# sodimm_perf.net
KiCad netlist of a schematic drawn in EAGLE
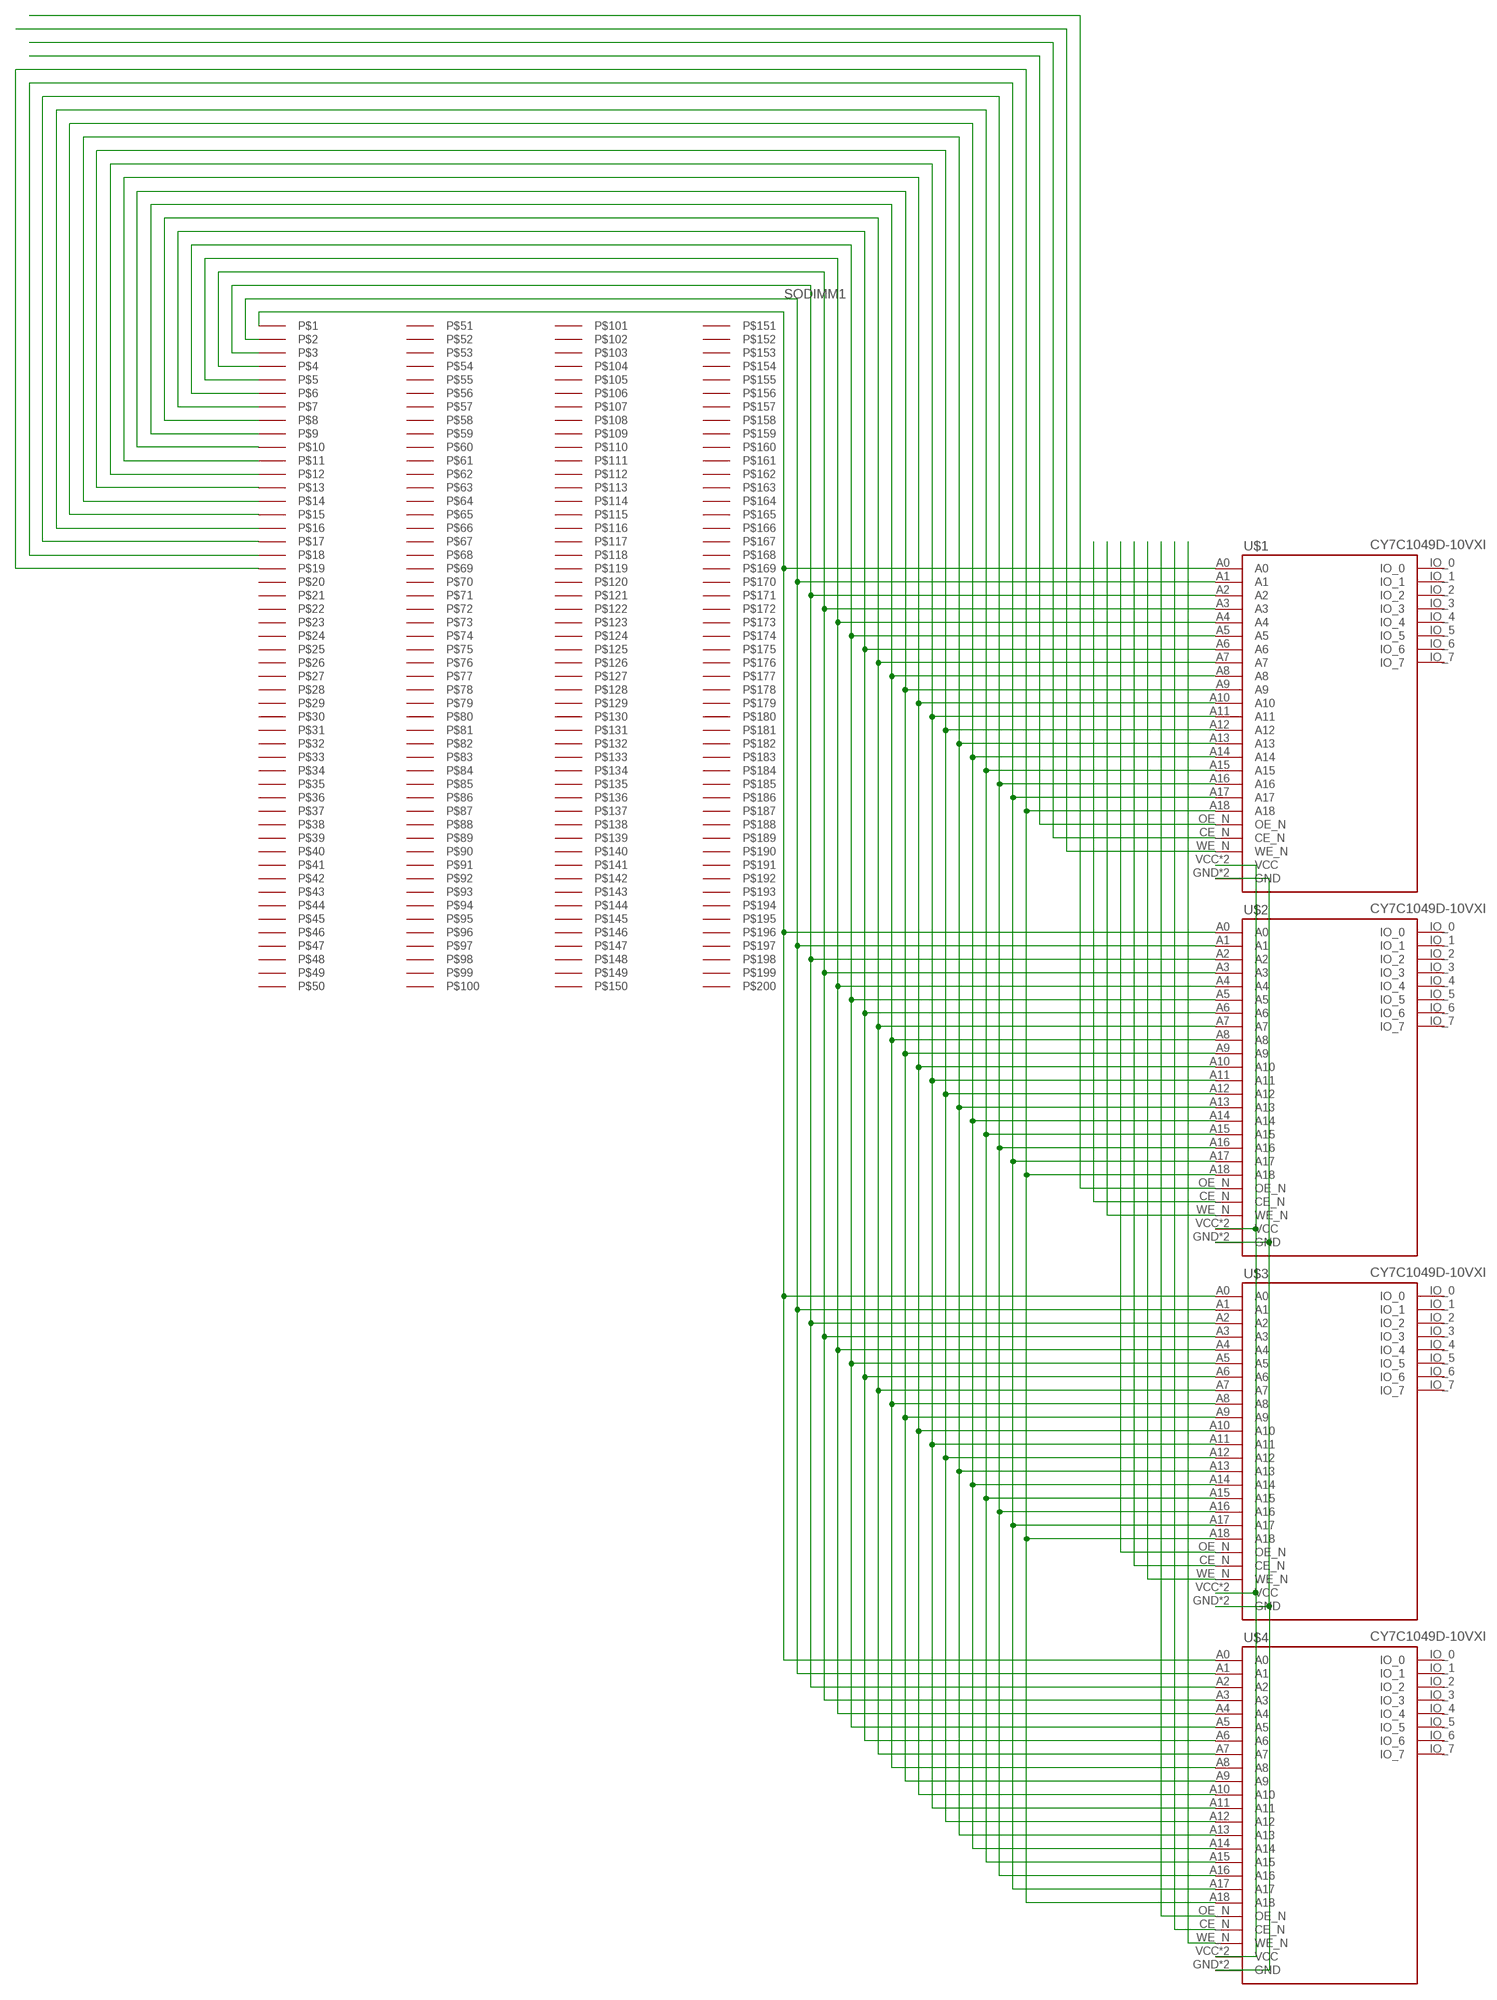
[diagram p0: schematic, sheet 1]

(export (version "E")
  (design (tool "Eeschema 10.0.6"))
  (components
    (comp (ref "SODIMM1")
      (value "SODIMM_BOARD")
      (footprint "eagle-import:SODIMM_BOARD-67.6X42.5")
      (libsource (lib "eagle-import") (part "SODIMM_BOARD"))
    )
    (comp (ref "U$1")
      (value "CY7C1049D-10VXI")
      (footprint "eagle-import:SOJ36")
      (libsource (lib "eagle-import") (part "CY7C1049D-10VXI"))
    )
    (comp (ref "U$2")
      (value "CY7C1049D-10VXI")
      (footprint "eagle-import:SOJ36")
      (libsource (lib "eagle-import") (part "CY7C1049D-10VXI"))
    )
    (comp (ref "U$3")
      (value "CY7C1049D-10VXI")
      (footprint "eagle-import:SOJ36")
      (libsource (lib "eagle-import") (part "CY7C1049D-10VXI"))
    )
    (comp (ref "U$4")
      (value "CY7C1049D-10VXI")
      (footprint "eagle-import:SOJ36")
      (libsource (lib "eagle-import") (part "CY7C1049D-10VXI"))
    )
  )
  (nets
    (net (code "1") (name "Net-(SODIMM1-P$1)") (class "Default")
      (node (ref "SODIMM1") (pin "1") (pinfunction "P$1_1") (pintype "bidirectional"))
      (node (ref "U$1") (pin "A0") (pinfunction "A0_A0") (pintype "input"))
      (node (ref "U$2") (pin "A0") (pinfunction "A0_A0") (pintype "input"))
      (node (ref "U$3") (pin "A0") (pinfunction "A0_A0") (pintype "input"))
      (node (ref "U$4") (pin "A0") (pinfunction "A0_A0") (pintype "input"))
    )
    (net (code "2") (name "Net-(SODIMM1-P$2)") (class "Default")
      (node (ref "SODIMM1") (pin "2") (pinfunction "P$2_2") (pintype "bidirectional"))
      (node (ref "U$1") (pin "A1") (pinfunction "A1_A1") (pintype "input"))
      (node (ref "U$2") (pin "A1") (pinfunction "A1_A1") (pintype "input"))
      (node (ref "U$3") (pin "A1") (pinfunction "A1_A1") (pintype "input"))
      (node (ref "U$4") (pin "A1") (pinfunction "A1_A1") (pintype "input"))
    )
    (net (code "3") (name "Net-(SODIMM1-P$3)") (class "Default")
      (node (ref "SODIMM1") (pin "3") (pinfunction "P$3_3") (pintype "bidirectional"))
      (node (ref "U$1") (pin "A2") (pinfunction "A2_A2") (pintype "input"))
      (node (ref "U$2") (pin "A2") (pinfunction "A2_A2") (pintype "input"))
      (node (ref "U$3") (pin "A2") (pinfunction "A2_A2") (pintype "input"))
      (node (ref "U$4") (pin "A2") (pinfunction "A2_A2") (pintype "input"))
    )
    (net (code "4") (name "Net-(SODIMM1-P$4)") (class "Default")
      (node (ref "SODIMM1") (pin "4") (pinfunction "P$4_4") (pintype "bidirectional"))
      (node (ref "U$1") (pin "A3") (pinfunction "A3_A3") (pintype "input"))
      (node (ref "U$2") (pin "A3") (pinfunction "A3_A3") (pintype "input"))
      (node (ref "U$3") (pin "A3") (pinfunction "A3_A3") (pintype "input"))
      (node (ref "U$4") (pin "A3") (pinfunction "A3_A3") (pintype "input"))
    )
    (net (code "5") (name "Net-(SODIMM1-P$5)") (class "Default")
      (node (ref "SODIMM1") (pin "5") (pinfunction "P$5_5") (pintype "bidirectional"))
      (node (ref "U$1") (pin "A4") (pinfunction "A4_A4") (pintype "input"))
      (node (ref "U$2") (pin "A4") (pinfunction "A4_A4") (pintype "input"))
      (node (ref "U$3") (pin "A4") (pinfunction "A4_A4") (pintype "input"))
      (node (ref "U$4") (pin "A4") (pinfunction "A4_A4") (pintype "input"))
    )
    (net (code "6") (name "Net-(SODIMM1-P$6)") (class "Default")
      (node (ref "SODIMM1") (pin "6") (pinfunction "P$6_6") (pintype "bidirectional"))
      (node (ref "U$1") (pin "A5") (pinfunction "A5_A5") (pintype "input"))
      (node (ref "U$2") (pin "A5") (pinfunction "A5_A5") (pintype "input"))
      (node (ref "U$3") (pin "A5") (pinfunction "A5_A5") (pintype "input"))
      (node (ref "U$4") (pin "A5") (pinfunction "A5_A5") (pintype "input"))
    )
    (net (code "7") (name "Net-(SODIMM1-P$7)") (class "Default")
      (node (ref "SODIMM1") (pin "7") (pinfunction "P$7_7") (pintype "bidirectional"))
      (node (ref "U$1") (pin "A6") (pinfunction "A6_A6") (pintype "input"))
      (node (ref "U$2") (pin "A6") (pinfunction "A6_A6") (pintype "input"))
      (node (ref "U$3") (pin "A6") (pinfunction "A6_A6") (pintype "input"))
      (node (ref "U$4") (pin "A6") (pinfunction "A6_A6") (pintype "input"))
    )
    (net (code "8") (name "Net-(SODIMM1-P$8)") (class "Default")
      (node (ref "SODIMM1") (pin "8") (pinfunction "P$8_8") (pintype "bidirectional"))
      (node (ref "U$1") (pin "A7") (pinfunction "A7_A7") (pintype "input"))
      (node (ref "U$2") (pin "A7") (pinfunction "A7_A7") (pintype "input"))
      (node (ref "U$3") (pin "A7") (pinfunction "A7_A7") (pintype "input"))
      (node (ref "U$4") (pin "A7") (pinfunction "A7_A7") (pintype "input"))
    )
    (net (code "9") (name "Net-(SODIMM1-P$9)") (class "Default")
      (node (ref "SODIMM1") (pin "9") (pinfunction "P$9_9") (pintype "bidirectional"))
      (node (ref "U$1") (pin "A8") (pinfunction "A8_A8") (pintype "input"))
      (node (ref "U$2") (pin "A8") (pinfunction "A8_A8") (pintype "input"))
      (node (ref "U$3") (pin "A8") (pinfunction "A8_A8") (pintype "input"))
      (node (ref "U$4") (pin "A8") (pinfunction "A8_A8") (pintype "input"))
    )
    (net (code "10") (name "Net-(SODIMM1-P$10)") (class "Default")
      (node (ref "SODIMM1") (pin "10") (pinfunction "P$10_10") (pintype "bidirectional"))
      (node (ref "U$1") (pin "A9") (pinfunction "A9_A9") (pintype "input"))
      (node (ref "U$2") (pin "A9") (pinfunction "A9_A9") (pintype "input"))
      (node (ref "U$3") (pin "A9") (pinfunction "A9_A9") (pintype "input"))
      (node (ref "U$4") (pin "A9") (pinfunction "A9_A9") (pintype "input"))
    )
    (net (code "11") (name "Net-(SODIMM1-P$11)") (class "Default")
      (node (ref "SODIMM1") (pin "11") (pinfunction "P$11_11") (pintype "bidirectional"))
      (node (ref "U$1") (pin "A10") (pinfunction "A10_A10") (pintype "input"))
      (node (ref "U$2") (pin "A10") (pinfunction "A10_A10") (pintype "input"))
      (node (ref "U$3") (pin "A10") (pinfunction "A10_A10") (pintype "input"))
      (node (ref "U$4") (pin "A10") (pinfunction "A10_A10") (pintype "input"))
    )
    (net (code "12") (name "Net-(SODIMM1-P$12)") (class "Default")
      (node (ref "SODIMM1") (pin "12") (pinfunction "P$12_12") (pintype "bidirectional"))
      (node (ref "U$1") (pin "A11") (pinfunction "A11_A11") (pintype "input"))
      (node (ref "U$2") (pin "A11") (pinfunction "A11_A11") (pintype "input"))
      (node (ref "U$3") (pin "A11") (pinfunction "A11_A11") (pintype "input"))
      (node (ref "U$4") (pin "A11") (pinfunction "A11_A11") (pintype "input"))
    )
    (net (code "13") (name "Net-(SODIMM1-P$13)") (class "Default")
      (node (ref "SODIMM1") (pin "13") (pinfunction "P$13_13") (pintype "bidirectional"))
      (node (ref "U$1") (pin "A12") (pinfunction "A12_A12") (pintype "input"))
      (node (ref "U$2") (pin "A12") (pinfunction "A12_A12") (pintype "input"))
      (node (ref "U$3") (pin "A12") (pinfunction "A12_A12") (pintype "input"))
      (node (ref "U$4") (pin "A12") (pinfunction "A12_A12") (pintype "input"))
    )
    (net (code "14") (name "Net-(SODIMM1-P$14)") (class "Default")
      (node (ref "SODIMM1") (pin "14") (pinfunction "P$14_14") (pintype "bidirectional"))
      (node (ref "U$1") (pin "A13") (pinfunction "A13_A13") (pintype "input"))
      (node (ref "U$2") (pin "A13") (pinfunction "A13_A13") (pintype "input"))
      (node (ref "U$3") (pin "A13") (pinfunction "A13_A13") (pintype "input"))
      (node (ref "U$4") (pin "A13") (pinfunction "A13_A13") (pintype "input"))
    )
    (net (code "15") (name "Net-(SODIMM1-P$15)") (class "Default")
      (node (ref "SODIMM1") (pin "15") (pinfunction "P$15_15") (pintype "bidirectional"))
      (node (ref "U$1") (pin "A14") (pinfunction "A14_A14") (pintype "input"))
      (node (ref "U$2") (pin "A14") (pinfunction "A14_A14") (pintype "input"))
      (node (ref "U$3") (pin "A14") (pinfunction "A14_A14") (pintype "input"))
      (node (ref "U$4") (pin "A14") (pinfunction "A14_A14") (pintype "input"))
    )
    (net (code "16") (name "Net-(SODIMM1-P$16)") (class "Default")
      (node (ref "SODIMM1") (pin "16") (pinfunction "P$16_16") (pintype "bidirectional"))
      (node (ref "U$1") (pin "A15") (pinfunction "A15_A15") (pintype "input"))
      (node (ref "U$2") (pin "A15") (pinfunction "A15_A15") (pintype "input"))
      (node (ref "U$3") (pin "A15") (pinfunction "A15_A15") (pintype "input"))
      (node (ref "U$4") (pin "A15") (pinfunction "A15_A15") (pintype "input"))
    )
    (net (code "17") (name "Net-(SODIMM1-P$17)") (class "Default")
      (node (ref "SODIMM1") (pin "17") (pinfunction "P$17_17") (pintype "bidirectional"))
      (node (ref "U$1") (pin "A16") (pinfunction "A16_A16") (pintype "input"))
      (node (ref "U$2") (pin "A16") (pinfunction "A16_A16") (pintype "input"))
      (node (ref "U$3") (pin "A16") (pinfunction "A16_A16") (pintype "input"))
      (node (ref "U$4") (pin "A16") (pinfunction "A16_A16") (pintype "input"))
    )
    (net (code "18") (name "Net-(SODIMM1-P$18)") (class "Default")
      (node (ref "SODIMM1") (pin "18") (pinfunction "P$18_18") (pintype "bidirectional"))
      (node (ref "U$1") (pin "A17") (pinfunction "A17_A17") (pintype "input"))
      (node (ref "U$2") (pin "A17") (pinfunction "A17_A17") (pintype "input"))
      (node (ref "U$3") (pin "A17") (pinfunction "A17_A17") (pintype "input"))
      (node (ref "U$4") (pin "A17") (pinfunction "A17_A17") (pintype "input"))
    )
    (net (code "19") (name "Net-(SODIMM1-P$19)") (class "Default")
      (node (ref "SODIMM1") (pin "19") (pinfunction "P$19_19") (pintype "bidirectional"))
      (node (ref "U$1") (pin "A18") (pinfunction "A18_A18") (pintype "input"))
      (node (ref "U$2") (pin "A18") (pinfunction "A18_A18") (pintype "input"))
      (node (ref "U$3") (pin "A18") (pinfunction "A18_A18") (pintype "input"))
      (node (ref "U$4") (pin "A18") (pinfunction "A18_A18") (pintype "input"))
    )
    (net (code "20") (name "Net-(U$1-GND-PadGND_)") (class "Default")
      (node (ref "U$1") (pin "GND") (pinfunction "GND_GND") (pintype "power_in"))
      (node (ref "U$1") (pin "GND_") (pinfunction "GND_GND_") (pintype "power_in"))
      (node (ref "U$2") (pin "GND") (pinfunction "GND_GND") (pintype "power_in"))
      (node (ref "U$2") (pin "GND_") (pinfunction "GND_GND_") (pintype "power_in"))
      (node (ref "U$3") (pin "GND") (pinfunction "GND_GND") (pintype "power_in"))
      (node (ref "U$3") (pin "GND_") (pinfunction "GND_GND_") (pintype "power_in"))
      (node (ref "U$4") (pin "GND") (pinfunction "GND_GND") (pintype "power_in"))
      (node (ref "U$4") (pin "GND_") (pinfunction "GND_GND_") (pintype "power_in"))
    )
    (net (code "21") (name "Net-(U$1-PadVCC)") (class "Default")
      (node (ref "U$1") (pin "VCC") (pinfunction "VCC_VCC") (pintype "power_in"))
      (node (ref "U$1") (pin "VCC_") (pinfunction "VCC_VCC_") (pintype "power_in"))
      (node (ref "U$2") (pin "VCC") (pinfunction "VCC_VCC") (pintype "power_in"))
      (node (ref "U$2") (pin "VCC_") (pinfunction "VCC_VCC_") (pintype "power_in"))
      (node (ref "U$3") (pin "VCC") (pinfunction "VCC_VCC") (pintype "power_in"))
      (node (ref "U$3") (pin "VCC_") (pinfunction "VCC_VCC_") (pintype "power_in"))
      (node (ref "U$4") (pin "VCC") (pinfunction "VCC_VCC") (pintype "power_in"))
      (node (ref "U$4") (pin "VCC_") (pinfunction "VCC_VCC_") (pintype "power_in"))
    )
    (net (code "22") (name "unconnected-(SODIMM1-P$20-Pad20)") (class "Default")
      (node (ref "SODIMM1") (pin "20") (pinfunction "P$20_20") (pintype "bidirectional"))
    )
    (net (code "23") (name "unconnected-(SODIMM1-P$21-Pad21)") (class "Default")
      (node (ref "SODIMM1") (pin "21") (pinfunction "P$21_21") (pintype "bidirectional"))
    )
    (net (code "24") (name "unconnected-(SODIMM1-P$22-Pad22)") (class "Default")
      (node (ref "SODIMM1") (pin "22") (pinfunction "P$22_22") (pintype "bidirectional"))
    )
    (net (code "25") (name "unconnected-(SODIMM1-P$23-Pad23)") (class "Default")
      (node (ref "SODIMM1") (pin "23") (pinfunction "P$23_23") (pintype "bidirectional"))
    )
    (net (code "26") (name "unconnected-(SODIMM1-P$24-Pad24)") (class "Default")
      (node (ref "SODIMM1") (pin "24") (pinfunction "P$24_24") (pintype "bidirectional"))
    )
    (net (code "27") (name "unconnected-(SODIMM1-P$25-Pad25)") (class "Default")
      (node (ref "SODIMM1") (pin "25") (pinfunction "P$25_25") (pintype "bidirectional"))
    )
    (net (code "28") (name "unconnected-(SODIMM1-P$26-Pad26)") (class "Default")
      (node (ref "SODIMM1") (pin "26") (pinfunction "P$26_26") (pintype "bidirectional"))
    )
    (net (code "29") (name "unconnected-(SODIMM1-P$27-Pad27)") (class "Default")
      (node (ref "SODIMM1") (pin "27") (pinfunction "P$27_27") (pintype "bidirectional"))
    )
    (net (code "30") (name "unconnected-(SODIMM1-P$28-Pad28)") (class "Default")
      (node (ref "SODIMM1") (pin "28") (pinfunction "P$28_28") (pintype "bidirectional"))
    )
    (net (code "31") (name "unconnected-(SODIMM1-P$29-Pad29)") (class "Default")
      (node (ref "SODIMM1") (pin "29") (pinfunction "P$29_29") (pintype "bidirectional"))
    )
    (net (code "32") (name "unconnected-(SODIMM1-P$30-Pad30)") (class "Default")
      (node (ref "SODIMM1") (pin "30") (pinfunction "P$30_30") (pintype "bidirectional"))
    )
    (net (code "33") (name "unconnected-(SODIMM1-P$31-Pad31)") (class "Default")
      (node (ref "SODIMM1") (pin "31") (pinfunction "P$31_31") (pintype "bidirectional"))
    )
    (net (code "34") (name "unconnected-(SODIMM1-P$32-Pad32)") (class "Default")
      (node (ref "SODIMM1") (pin "32") (pinfunction "P$32_32") (pintype "bidirectional"))
    )
    (net (code "35") (name "unconnected-(SODIMM1-P$33-Pad33)") (class "Default")
      (node (ref "SODIMM1") (pin "33") (pinfunction "P$33_33") (pintype "bidirectional"))
    )
    (net (code "36") (name "unconnected-(SODIMM1-P$34-Pad34)") (class "Default")
      (node (ref "SODIMM1") (pin "34") (pinfunction "P$34_34") (pintype "bidirectional"))
    )
    (net (code "37") (name "unconnected-(SODIMM1-P$35-Pad35)") (class "Default")
      (node (ref "SODIMM1") (pin "35") (pinfunction "P$35_35") (pintype "bidirectional"))
    )
    (net (code "38") (name "unconnected-(SODIMM1-P$36-Pad36)") (class "Default")
      (node (ref "SODIMM1") (pin "36") (pinfunction "P$36_36") (pintype "bidirectional"))
    )
    (net (code "39") (name "unconnected-(SODIMM1-P$37-Pad37)") (class "Default")
      (node (ref "SODIMM1") (pin "37") (pinfunction "P$37_37") (pintype "bidirectional"))
    )
    (net (code "40") (name "unconnected-(SODIMM1-P$38-Pad38)") (class "Default")
      (node (ref "SODIMM1") (pin "38") (pinfunction "P$38_38") (pintype "bidirectional"))
    )
    (net (code "41") (name "unconnected-(SODIMM1-P$39-Pad39)") (class "Default")
      (node (ref "SODIMM1") (pin "39") (pinfunction "P$39_39") (pintype "bidirectional"))
    )
    (net (code "42") (name "unconnected-(SODIMM1-P$40-Pad40)") (class "Default")
      (node (ref "SODIMM1") (pin "40") (pinfunction "P$40_40") (pintype "bidirectional"))
    )
    (net (code "43") (name "unconnected-(SODIMM1-P$41-Pad41)") (class "Default")
      (node (ref "SODIMM1") (pin "41") (pinfunction "P$41_41") (pintype "bidirectional"))
    )
    (net (code "44") (name "unconnected-(SODIMM1-P$42-Pad42)") (class "Default")
      (node (ref "SODIMM1") (pin "42") (pinfunction "P$42_42") (pintype "bidirectional"))
    )
    (net (code "45") (name "unconnected-(SODIMM1-P$43-Pad43)") (class "Default")
      (node (ref "SODIMM1") (pin "43") (pinfunction "P$43_43") (pintype "bidirectional"))
    )
    (net (code "46") (name "unconnected-(SODIMM1-P$44-Pad44)") (class "Default")
      (node (ref "SODIMM1") (pin "44") (pinfunction "P$44_44") (pintype "bidirectional"))
    )
    (net (code "47") (name "unconnected-(SODIMM1-P$45-Pad45)") (class "Default")
      (node (ref "SODIMM1") (pin "45") (pinfunction "P$45_45") (pintype "bidirectional"))
    )
    (net (code "48") (name "unconnected-(SODIMM1-P$46-Pad46)") (class "Default")
      (node (ref "SODIMM1") (pin "46") (pinfunction "P$46_46") (pintype "bidirectional"))
    )
    (net (code "49") (name "unconnected-(SODIMM1-P$47-Pad47)") (class "Default")
      (node (ref "SODIMM1") (pin "47") (pinfunction "P$47_47") (pintype "bidirectional"))
    )
    (net (code "50") (name "unconnected-(SODIMM1-P$48-Pad48)") (class "Default")
      (node (ref "SODIMM1") (pin "48") (pinfunction "P$48_48") (pintype "bidirectional"))
    )
    (net (code "51") (name "unconnected-(SODIMM1-P$49-Pad49)") (class "Default")
      (node (ref "SODIMM1") (pin "49") (pinfunction "P$49_49") (pintype "bidirectional"))
    )
    (net (code "52") (name "unconnected-(SODIMM1-P$50-Pad50)") (class "Default")
      (node (ref "SODIMM1") (pin "50") (pinfunction "P$50_50") (pintype "bidirectional"))
    )
    (net (code "53") (name "unconnected-(SODIMM1-P$51-Pad51)") (class "Default")
      (node (ref "SODIMM1") (pin "51") (pinfunction "P$51_51") (pintype "bidirectional"))
    )
    (net (code "54") (name "unconnected-(SODIMM1-P$52-Pad52)") (class "Default")
      (node (ref "SODIMM1") (pin "52") (pinfunction "P$52_52") (pintype "bidirectional"))
    )
    (net (code "55") (name "unconnected-(SODIMM1-P$53-Pad53)") (class "Default")
      (node (ref "SODIMM1") (pin "53") (pinfunction "P$53_53") (pintype "bidirectional"))
    )
    (net (code "56") (name "unconnected-(SODIMM1-P$54-Pad54)") (class "Default")
      (node (ref "SODIMM1") (pin "54") (pinfunction "P$54_54") (pintype "bidirectional"))
    )
    (net (code "57") (name "unconnected-(SODIMM1-P$55-Pad55)") (class "Default")
      (node (ref "SODIMM1") (pin "55") (pinfunction "P$55_55") (pintype "bidirectional"))
    )
    (net (code "58") (name "unconnected-(SODIMM1-P$56-Pad56)") (class "Default")
      (node (ref "SODIMM1") (pin "56") (pinfunction "P$56_56") (pintype "bidirectional"))
    )
    (net (code "59") (name "unconnected-(SODIMM1-P$57-Pad57)") (class "Default")
      (node (ref "SODIMM1") (pin "57") (pinfunction "P$57_57") (pintype "bidirectional"))
    )
    (net (code "60") (name "unconnected-(SODIMM1-P$58-Pad58)") (class "Default")
      (node (ref "SODIMM1") (pin "58") (pinfunction "P$58_58") (pintype "bidirectional"))
    )
    (net (code "61") (name "unconnected-(SODIMM1-P$59-Pad59)") (class "Default")
      (node (ref "SODIMM1") (pin "59") (pinfunction "P$59_59") (pintype "bidirectional"))
    )
    (net (code "62") (name "unconnected-(SODIMM1-P$60-Pad60)") (class "Default")
      (node (ref "SODIMM1") (pin "60") (pinfunction "P$60_60") (pintype "bidirectional"))
    )
    (net (code "63") (name "unconnected-(SODIMM1-P$61-Pad61)") (class "Default")
      (node (ref "SODIMM1") (pin "61") (pinfunction "P$61_61") (pintype "bidirectional"))
    )
    (net (code "64") (name "unconnected-(SODIMM1-P$62-Pad62)") (class "Default")
      (node (ref "SODIMM1") (pin "62") (pinfunction "P$62_62") (pintype "bidirectional"))
    )
    (net (code "65") (name "unconnected-(SODIMM1-P$63-Pad63)") (class "Default")
      (node (ref "SODIMM1") (pin "63") (pinfunction "P$63_63") (pintype "bidirectional"))
    )
    (net (code "66") (name "unconnected-(SODIMM1-P$64-Pad64)") (class "Default")
      (node (ref "SODIMM1") (pin "64") (pinfunction "P$64_64") (pintype "bidirectional"))
    )
    (net (code "67") (name "unconnected-(SODIMM1-P$65-Pad65)") (class "Default")
      (node (ref "SODIMM1") (pin "65") (pinfunction "P$65_65") (pintype "bidirectional"))
    )
    (net (code "68") (name "unconnected-(SODIMM1-P$66-Pad66)") (class "Default")
      (node (ref "SODIMM1") (pin "66") (pinfunction "P$66_66") (pintype "bidirectional"))
    )
    (net (code "69") (name "unconnected-(SODIMM1-P$67-Pad67)") (class "Default")
      (node (ref "SODIMM1") (pin "67") (pinfunction "P$67_67") (pintype "bidirectional"))
    )
    (net (code "70") (name "unconnected-(SODIMM1-P$68-Pad68)") (class "Default")
      (node (ref "SODIMM1") (pin "68") (pinfunction "P$68_68") (pintype "bidirectional"))
    )
    (net (code "71") (name "unconnected-(SODIMM1-P$69-Pad69)") (class "Default")
      (node (ref "SODIMM1") (pin "69") (pinfunction "P$69_69") (pintype "bidirectional"))
    )
    (net (code "72") (name "unconnected-(SODIMM1-P$70-Pad70)") (class "Default")
      (node (ref "SODIMM1") (pin "70") (pinfunction "P$70_70") (pintype "bidirectional"))
    )
    (net (code "73") (name "unconnected-(SODIMM1-P$71-Pad71)") (class "Default")
      (node (ref "SODIMM1") (pin "71") (pinfunction "P$71_71") (pintype "bidirectional"))
    )
    (net (code "74") (name "unconnected-(SODIMM1-P$72-Pad72)") (class "Default")
      (node (ref "SODIMM1") (pin "72") (pinfunction "P$72_72") (pintype "bidirectional"))
    )
    (net (code "75") (name "unconnected-(SODIMM1-P$73-Pad73)") (class "Default")
      (node (ref "SODIMM1") (pin "73") (pinfunction "P$73_73") (pintype "bidirectional"))
    )
    (net (code "76") (name "unconnected-(SODIMM1-P$74-Pad74)") (class "Default")
      (node (ref "SODIMM1") (pin "74") (pinfunction "P$74_74") (pintype "bidirectional"))
    )
    (net (code "77") (name "unconnected-(SODIMM1-P$75-Pad75)") (class "Default")
      (node (ref "SODIMM1") (pin "75") (pinfunction "P$75_75") (pintype "bidirectional"))
    )
    (net (code "78") (name "unconnected-(SODIMM1-P$76-Pad76)") (class "Default")
      (node (ref "SODIMM1") (pin "76") (pinfunction "P$76_76") (pintype "bidirectional"))
    )
    (net (code "79") (name "unconnected-(SODIMM1-P$77-Pad77)") (class "Default")
      (node (ref "SODIMM1") (pin "77") (pinfunction "P$77_77") (pintype "bidirectional"))
    )
    (net (code "80") (name "unconnected-(SODIMM1-P$78-Pad78)") (class "Default")
      (node (ref "SODIMM1") (pin "78") (pinfunction "P$78_78") (pintype "bidirectional"))
    )
    (net (code "81") (name "unconnected-(SODIMM1-P$79-Pad79)") (class "Default")
      (node (ref "SODIMM1") (pin "79") (pinfunction "P$79_79") (pintype "bidirectional"))
    )
    (net (code "82") (name "unconnected-(SODIMM1-P$80-Pad80)") (class "Default")
      (node (ref "SODIMM1") (pin "80") (pinfunction "P$80_80") (pintype "bidirectional"))
    )
    (net (code "83") (name "unconnected-(SODIMM1-P$81-Pad81)") (class "Default")
      (node (ref "SODIMM1") (pin "81") (pinfunction "P$81_81") (pintype "bidirectional"))
    )
    (net (code "84") (name "unconnected-(SODIMM1-P$82-Pad82)") (class "Default")
      (node (ref "SODIMM1") (pin "82") (pinfunction "P$82_82") (pintype "bidirectional"))
    )
    (net (code "85") (name "unconnected-(SODIMM1-P$83-Pad83)") (class "Default")
      (node (ref "SODIMM1") (pin "83") (pinfunction "P$83_83") (pintype "bidirectional"))
    )
    (net (code "86") (name "unconnected-(SODIMM1-P$84-Pad84)") (class "Default")
      (node (ref "SODIMM1") (pin "84") (pinfunction "P$84_84") (pintype "bidirectional"))
    )
    (net (code "87") (name "unconnected-(SODIMM1-P$85-Pad85)") (class "Default")
      (node (ref "SODIMM1") (pin "85") (pinfunction "P$85_85") (pintype "bidirectional"))
    )
    (net (code "88") (name "unconnected-(SODIMM1-P$86-Pad86)") (class "Default")
      (node (ref "SODIMM1") (pin "86") (pinfunction "P$86_86") (pintype "bidirectional"))
    )
    (net (code "89") (name "unconnected-(SODIMM1-P$87-Pad87)") (class "Default")
      (node (ref "SODIMM1") (pin "87") (pinfunction "P$87_87") (pintype "bidirectional"))
    )
    (net (code "90") (name "unconnected-(SODIMM1-P$88-Pad88)") (class "Default")
      (node (ref "SODIMM1") (pin "88") (pinfunction "P$88_88") (pintype "bidirectional"))
    )
    (net (code "91") (name "unconnected-(SODIMM1-P$89-Pad89)") (class "Default")
      (node (ref "SODIMM1") (pin "89") (pinfunction "P$89_89") (pintype "bidirectional"))
    )
    (net (code "92") (name "unconnected-(SODIMM1-P$90-Pad90)") (class "Default")
      (node (ref "SODIMM1") (pin "90") (pinfunction "P$90_90") (pintype "bidirectional"))
    )
    (net (code "93") (name "unconnected-(SODIMM1-P$91-Pad91)") (class "Default")
      (node (ref "SODIMM1") (pin "91") (pinfunction "P$91_91") (pintype "bidirectional"))
    )
    (net (code "94") (name "unconnected-(SODIMM1-P$92-Pad92)") (class "Default")
      (node (ref "SODIMM1") (pin "92") (pinfunction "P$92_92") (pintype "bidirectional"))
    )
    (net (code "95") (name "unconnected-(SODIMM1-P$93-Pad93)") (class "Default")
      (node (ref "SODIMM1") (pin "93") (pinfunction "P$93_93") (pintype "bidirectional"))
    )
    (net (code "96") (name "unconnected-(SODIMM1-P$94-Pad94)") (class "Default")
      (node (ref "SODIMM1") (pin "94") (pinfunction "P$94_94") (pintype "bidirectional"))
    )
    (net (code "97") (name "unconnected-(SODIMM1-P$95-Pad95)") (class "Default")
      (node (ref "SODIMM1") (pin "95") (pinfunction "P$95_95") (pintype "bidirectional"))
    )
    (net (code "98") (name "unconnected-(SODIMM1-P$96-Pad96)") (class "Default")
      (node (ref "SODIMM1") (pin "96") (pinfunction "P$96_96") (pintype "bidirectional"))
    )
    (net (code "99") (name "unconnected-(SODIMM1-P$97-Pad97)") (class "Default")
      (node (ref "SODIMM1") (pin "97") (pinfunction "P$97_97") (pintype "bidirectional"))
    )
    (net (code "100") (name "unconnected-(SODIMM1-P$98-Pad98)") (class "Default")
      (node (ref "SODIMM1") (pin "98") (pinfunction "P$98_98") (pintype "bidirectional"))
    )
    (net (code "101") (name "unconnected-(SODIMM1-P$99-Pad99)") (class "Default")
      (node (ref "SODIMM1") (pin "99") (pinfunction "P$99_99") (pintype "bidirectional"))
    )
    (net (code "102") (name "unconnected-(SODIMM1-P$100-Pad100)") (class "Default")
      (node (ref "SODIMM1") (pin "100") (pinfunction "P$100_100") (pintype "bidirectional"))
    )
    (net (code "103") (name "unconnected-(SODIMM1-P$101-Pad101)") (class "Default")
      (node (ref "SODIMM1") (pin "101") (pinfunction "P$101_101") (pintype "bidirectional"))
    )
    (net (code "104") (name "unconnected-(SODIMM1-P$102-Pad102)") (class "Default")
      (node (ref "SODIMM1") (pin "102") (pinfunction "P$102_102") (pintype "bidirectional"))
    )
    (net (code "105") (name "unconnected-(SODIMM1-P$103-Pad103)") (class "Default")
      (node (ref "SODIMM1") (pin "103") (pinfunction "P$103_103") (pintype "bidirectional"))
    )
    (net (code "106") (name "unconnected-(SODIMM1-P$104-Pad104)") (class "Default")
      (node (ref "SODIMM1") (pin "104") (pinfunction "P$104_104") (pintype "bidirectional"))
    )
    (net (code "107") (name "unconnected-(SODIMM1-P$105-Pad105)") (class "Default")
      (node (ref "SODIMM1") (pin "105") (pinfunction "P$105_105") (pintype "bidirectional"))
    )
    (net (code "108") (name "unconnected-(SODIMM1-P$106-Pad106)") (class "Default")
      (node (ref "SODIMM1") (pin "106") (pinfunction "P$106_106") (pintype "bidirectional"))
    )
    (net (code "109") (name "unconnected-(SODIMM1-P$107-Pad107)") (class "Default")
      (node (ref "SODIMM1") (pin "107") (pinfunction "P$107_107") (pintype "bidirectional"))
    )
    (net (code "110") (name "unconnected-(SODIMM1-P$108-Pad108)") (class "Default")
      (node (ref "SODIMM1") (pin "108") (pinfunction "P$108_108") (pintype "bidirectional"))
    )
    (net (code "111") (name "unconnected-(SODIMM1-P$109-Pad109)") (class "Default")
      (node (ref "SODIMM1") (pin "109") (pinfunction "P$109_109") (pintype "bidirectional"))
    )
    (net (code "112") (name "unconnected-(SODIMM1-P$110-Pad110)") (class "Default")
      (node (ref "SODIMM1") (pin "110") (pinfunction "P$110_110") (pintype "bidirectional"))
    )
    (net (code "113") (name "unconnected-(SODIMM1-P$111-Pad111)") (class "Default")
      (node (ref "SODIMM1") (pin "111") (pinfunction "P$111_111") (pintype "bidirectional"))
    )
    (net (code "114") (name "unconnected-(SODIMM1-P$112-Pad112)") (class "Default")
      (node (ref "SODIMM1") (pin "112") (pinfunction "P$112_112") (pintype "bidirectional"))
    )
    (net (code "115") (name "unconnected-(SODIMM1-P$113-Pad113)") (class "Default")
      (node (ref "SODIMM1") (pin "113") (pinfunction "P$113_113") (pintype "bidirectional"))
    )
    (net (code "116") (name "unconnected-(SODIMM1-P$114-Pad114)") (class "Default")
      (node (ref "SODIMM1") (pin "114") (pinfunction "P$114_114") (pintype "bidirectional"))
    )
    (net (code "117") (name "unconnected-(SODIMM1-P$115-Pad115)") (class "Default")
      (node (ref "SODIMM1") (pin "115") (pinfunction "P$115_115") (pintype "bidirectional"))
    )
    (net (code "118") (name "unconnected-(SODIMM1-P$116-Pad116)") (class "Default")
      (node (ref "SODIMM1") (pin "116") (pinfunction "P$116_116") (pintype "bidirectional"))
    )
    (net (code "119") (name "unconnected-(SODIMM1-P$117-Pad117)") (class "Default")
      (node (ref "SODIMM1") (pin "117") (pinfunction "P$117_117") (pintype "bidirectional"))
    )
    (net (code "120") (name "unconnected-(SODIMM1-P$118-Pad118)") (class "Default")
      (node (ref "SODIMM1") (pin "118") (pinfunction "P$118_118") (pintype "bidirectional"))
    )
    (net (code "121") (name "unconnected-(SODIMM1-P$119-Pad119)") (class "Default")
      (node (ref "SODIMM1") (pin "119") (pinfunction "P$119_119") (pintype "bidirectional"))
    )
    (net (code "122") (name "unconnected-(SODIMM1-P$120-Pad120)") (class "Default")
      (node (ref "SODIMM1") (pin "120") (pinfunction "P$120_120") (pintype "bidirectional"))
    )
    (net (code "123") (name "unconnected-(SODIMM1-P$121-Pad121)") (class "Default")
      (node (ref "SODIMM1") (pin "121") (pinfunction "P$121_121") (pintype "bidirectional"))
    )
    (net (code "124") (name "unconnected-(SODIMM1-P$122-Pad122)") (class "Default")
      (node (ref "SODIMM1") (pin "122") (pinfunction "P$122_122") (pintype "bidirectional"))
    )
    (net (code "125") (name "unconnected-(SODIMM1-P$123-Pad123)") (class "Default")
      (node (ref "SODIMM1") (pin "123") (pinfunction "P$123_123") (pintype "bidirectional"))
    )
    (net (code "126") (name "unconnected-(SODIMM1-P$124-Pad124)") (class "Default")
      (node (ref "SODIMM1") (pin "124") (pinfunction "P$124_124") (pintype "bidirectional"))
    )
    (net (code "127") (name "unconnected-(SODIMM1-P$125-Pad125)") (class "Default")
      (node (ref "SODIMM1") (pin "125") (pinfunction "P$125_125") (pintype "bidirectional"))
    )
    (net (code "128") (name "unconnected-(SODIMM1-P$126-Pad126)") (class "Default")
      (node (ref "SODIMM1") (pin "126") (pinfunction "P$126_126") (pintype "bidirectional"))
    )
    (net (code "129") (name "unconnected-(SODIMM1-P$127-Pad127)") (class "Default")
      (node (ref "SODIMM1") (pin "127") (pinfunction "P$127_127") (pintype "bidirectional"))
    )
    (net (code "130") (name "unconnected-(SODIMM1-P$128-Pad128)") (class "Default")
      (node (ref "SODIMM1") (pin "128") (pinfunction "P$128_128") (pintype "bidirectional"))
    )
    (net (code "131") (name "unconnected-(SODIMM1-P$129-Pad129)") (class "Default")
      (node (ref "SODIMM1") (pin "129") (pinfunction "P$129_129") (pintype "bidirectional"))
    )
    (net (code "132") (name "unconnected-(SODIMM1-P$130-Pad130)") (class "Default")
      (node (ref "SODIMM1") (pin "130") (pinfunction "P$130_130") (pintype "bidirectional"))
    )
    (net (code "133") (name "unconnected-(SODIMM1-P$131-Pad131)") (class "Default")
      (node (ref "SODIMM1") (pin "131") (pinfunction "P$131_131") (pintype "bidirectional"))
    )
    (net (code "134") (name "unconnected-(SODIMM1-P$132-Pad132)") (class "Default")
      (node (ref "SODIMM1") (pin "132") (pinfunction "P$132_132") (pintype "bidirectional"))
    )
    (net (code "135") (name "unconnected-(SODIMM1-P$133-Pad133)") (class "Default")
      (node (ref "SODIMM1") (pin "133") (pinfunction "P$133_133") (pintype "bidirectional"))
    )
    (net (code "136") (name "unconnected-(SODIMM1-P$134-Pad134)") (class "Default")
      (node (ref "SODIMM1") (pin "134") (pinfunction "P$134_134") (pintype "bidirectional"))
    )
    (net (code "137") (name "unconnected-(SODIMM1-P$135-Pad135)") (class "Default")
      (node (ref "SODIMM1") (pin "135") (pinfunction "P$135_135") (pintype "bidirectional"))
    )
    (net (code "138") (name "unconnected-(SODIMM1-P$136-Pad136)") (class "Default")
      (node (ref "SODIMM1") (pin "136") (pinfunction "P$136_136") (pintype "bidirectional"))
    )
    (net (code "139") (name "unconnected-(SODIMM1-P$137-Pad137)") (class "Default")
      (node (ref "SODIMM1") (pin "137") (pinfunction "P$137_137") (pintype "bidirectional"))
    )
    (net (code "140") (name "unconnected-(SODIMM1-P$138-Pad138)") (class "Default")
      (node (ref "SODIMM1") (pin "138") (pinfunction "P$138_138") (pintype "bidirectional"))
    )
    (net (code "141") (name "unconnected-(SODIMM1-P$139-Pad139)") (class "Default")
      (node (ref "SODIMM1") (pin "139") (pinfunction "P$139_139") (pintype "bidirectional"))
    )
    (net (code "142") (name "unconnected-(SODIMM1-P$140-Pad140)") (class "Default")
      (node (ref "SODIMM1") (pin "140") (pinfunction "P$140_140") (pintype "bidirectional"))
    )
    (net (code "143") (name "unconnected-(SODIMM1-P$141-Pad141)") (class "Default")
      (node (ref "SODIMM1") (pin "141") (pinfunction "P$141_141") (pintype "bidirectional"))
    )
    (net (code "144") (name "unconnected-(SODIMM1-P$142-Pad142)") (class "Default")
      (node (ref "SODIMM1") (pin "142") (pinfunction "P$142_142") (pintype "bidirectional"))
    )
    (net (code "145") (name "unconnected-(SODIMM1-P$143-Pad143)") (class "Default")
      (node (ref "SODIMM1") (pin "143") (pinfunction "P$143_143") (pintype "bidirectional"))
    )
    (net (code "146") (name "unconnected-(SODIMM1-P$144-Pad144)") (class "Default")
      (node (ref "SODIMM1") (pin "144") (pinfunction "P$144_144") (pintype "bidirectional"))
    )
    (net (code "147") (name "unconnected-(SODIMM1-P$145-Pad145)") (class "Default")
      (node (ref "SODIMM1") (pin "145") (pinfunction "P$145_145") (pintype "bidirectional"))
    )
    (net (code "148") (name "unconnected-(SODIMM1-P$146-Pad146)") (class "Default")
      (node (ref "SODIMM1") (pin "146") (pinfunction "P$146_146") (pintype "bidirectional"))
    )
    (net (code "149") (name "unconnected-(SODIMM1-P$147-Pad147)") (class "Default")
      (node (ref "SODIMM1") (pin "147") (pinfunction "P$147_147") (pintype "bidirectional"))
    )
    (net (code "150") (name "unconnected-(SODIMM1-P$148-Pad148)") (class "Default")
      (node (ref "SODIMM1") (pin "148") (pinfunction "P$148_148") (pintype "bidirectional"))
    )
    (net (code "151") (name "unconnected-(SODIMM1-P$149-Pad149)") (class "Default")
      (node (ref "SODIMM1") (pin "149") (pinfunction "P$149_149") (pintype "bidirectional"))
    )
    (net (code "152") (name "unconnected-(SODIMM1-P$150-Pad150)") (class "Default")
      (node (ref "SODIMM1") (pin "150") (pinfunction "P$150_150") (pintype "bidirectional"))
    )
    (net (code "153") (name "unconnected-(SODIMM1-P$151-Pad151)") (class "Default")
      (node (ref "SODIMM1") (pin "151") (pinfunction "P$151_151") (pintype "bidirectional"))
    )
    (net (code "154") (name "unconnected-(SODIMM1-P$152-Pad152)") (class "Default")
      (node (ref "SODIMM1") (pin "152") (pinfunction "P$152_152") (pintype "bidirectional"))
    )
    (net (code "155") (name "unconnected-(SODIMM1-P$153-Pad153)") (class "Default")
      (node (ref "SODIMM1") (pin "153") (pinfunction "P$153_153") (pintype "bidirectional"))
    )
    (net (code "156") (name "unconnected-(SODIMM1-P$154-Pad154)") (class "Default")
      (node (ref "SODIMM1") (pin "154") (pinfunction "P$154_154") (pintype "bidirectional"))
    )
    (net (code "157") (name "unconnected-(SODIMM1-P$155-Pad155)") (class "Default")
      (node (ref "SODIMM1") (pin "155") (pinfunction "P$155_155") (pintype "bidirectional"))
    )
    (net (code "158") (name "unconnected-(SODIMM1-P$156-Pad156)") (class "Default")
      (node (ref "SODIMM1") (pin "156") (pinfunction "P$156_156") (pintype "bidirectional"))
    )
    (net (code "159") (name "unconnected-(SODIMM1-P$157-Pad157)") (class "Default")
      (node (ref "SODIMM1") (pin "157") (pinfunction "P$157_157") (pintype "bidirectional"))
    )
    (net (code "160") (name "unconnected-(SODIMM1-P$158-Pad158)") (class "Default")
      (node (ref "SODIMM1") (pin "158") (pinfunction "P$158_158") (pintype "bidirectional"))
    )
    (net (code "161") (name "unconnected-(SODIMM1-P$159-Pad159)") (class "Default")
      (node (ref "SODIMM1") (pin "159") (pinfunction "P$159_159") (pintype "bidirectional"))
    )
    (net (code "162") (name "unconnected-(SODIMM1-P$160-Pad160)") (class "Default")
      (node (ref "SODIMM1") (pin "160") (pinfunction "P$160_160") (pintype "bidirectional"))
    )
    (net (code "163") (name "unconnected-(SODIMM1-P$161-Pad161)") (class "Default")
      (node (ref "SODIMM1") (pin "161") (pinfunction "P$161_161") (pintype "bidirectional"))
    )
    (net (code "164") (name "unconnected-(SODIMM1-P$162-Pad162)") (class "Default")
      (node (ref "SODIMM1") (pin "162") (pinfunction "P$162_162") (pintype "bidirectional"))
    )
    (net (code "165") (name "unconnected-(SODIMM1-P$163-Pad163)") (class "Default")
      (node (ref "SODIMM1") (pin "163") (pinfunction "P$163_163") (pintype "bidirectional"))
    )
    (net (code "166") (name "unconnected-(SODIMM1-P$164-Pad164)") (class "Default")
      (node (ref "SODIMM1") (pin "164") (pinfunction "P$164_164") (pintype "bidirectional"))
    )
    (net (code "167") (name "unconnected-(SODIMM1-P$165-Pad165)") (class "Default")
      (node (ref "SODIMM1") (pin "165") (pinfunction "P$165_165") (pintype "bidirectional"))
    )
    (net (code "168") (name "unconnected-(SODIMM1-P$166-Pad166)") (class "Default")
      (node (ref "SODIMM1") (pin "166") (pinfunction "P$166_166") (pintype "bidirectional"))
    )
    (net (code "169") (name "unconnected-(SODIMM1-P$167-Pad167)") (class "Default")
      (node (ref "SODIMM1") (pin "167") (pinfunction "P$167_167") (pintype "bidirectional"))
    )
    (net (code "170") (name "unconnected-(SODIMM1-P$168-Pad168)") (class "Default")
      (node (ref "SODIMM1") (pin "168") (pinfunction "P$168_168") (pintype "bidirectional"))
    )
    (net (code "171") (name "unconnected-(SODIMM1-P$169-Pad169)") (class "Default")
      (node (ref "SODIMM1") (pin "169") (pinfunction "P$169_169") (pintype "bidirectional"))
    )
    (net (code "172") (name "unconnected-(SODIMM1-P$170-Pad170)") (class "Default")
      (node (ref "SODIMM1") (pin "170") (pinfunction "P$170_170") (pintype "bidirectional"))
    )
    (net (code "173") (name "unconnected-(SODIMM1-P$171-Pad171)") (class "Default")
      (node (ref "SODIMM1") (pin "171") (pinfunction "P$171_171") (pintype "bidirectional"))
    )
    (net (code "174") (name "unconnected-(SODIMM1-P$172-Pad172)") (class "Default")
      (node (ref "SODIMM1") (pin "172") (pinfunction "P$172_172") (pintype "bidirectional"))
    )
    (net (code "175") (name "unconnected-(SODIMM1-P$173-Pad173)") (class "Default")
      (node (ref "SODIMM1") (pin "173") (pinfunction "P$173_173") (pintype "bidirectional"))
    )
    (net (code "176") (name "unconnected-(SODIMM1-P$174-Pad174)") (class "Default")
      (node (ref "SODIMM1") (pin "174") (pinfunction "P$174_174") (pintype "bidirectional"))
    )
    (net (code "177") (name "unconnected-(SODIMM1-P$175-Pad175)") (class "Default")
      (node (ref "SODIMM1") (pin "175") (pinfunction "P$175_175") (pintype "bidirectional"))
    )
    (net (code "178") (name "unconnected-(SODIMM1-P$176-Pad176)") (class "Default")
      (node (ref "SODIMM1") (pin "176") (pinfunction "P$176_176") (pintype "bidirectional"))
    )
    (net (code "179") (name "unconnected-(SODIMM1-P$177-Pad177)") (class "Default")
      (node (ref "SODIMM1") (pin "177") (pinfunction "P$177_177") (pintype "bidirectional"))
    )
    (net (code "180") (name "unconnected-(SODIMM1-P$178-Pad178)") (class "Default")
      (node (ref "SODIMM1") (pin "178") (pinfunction "P$178_178") (pintype "bidirectional"))
    )
    (net (code "181") (name "unconnected-(SODIMM1-P$179-Pad179)") (class "Default")
      (node (ref "SODIMM1") (pin "179") (pinfunction "P$179_179") (pintype "bidirectional"))
    )
    (net (code "182") (name "unconnected-(SODIMM1-P$180-Pad180)") (class "Default")
      (node (ref "SODIMM1") (pin "180") (pinfunction "P$180_180") (pintype "bidirectional"))
    )
    (net (code "183") (name "unconnected-(SODIMM1-P$181-Pad181)") (class "Default")
      (node (ref "SODIMM1") (pin "181") (pinfunction "P$181_181") (pintype "bidirectional"))
    )
    (net (code "184") (name "unconnected-(SODIMM1-P$182-Pad182)") (class "Default")
      (node (ref "SODIMM1") (pin "182") (pinfunction "P$182_182") (pintype "bidirectional"))
    )
    (net (code "185") (name "unconnected-(SODIMM1-P$183-Pad183)") (class "Default")
      (node (ref "SODIMM1") (pin "183") (pinfunction "P$183_183") (pintype "bidirectional"))
    )
    (net (code "186") (name "unconnected-(SODIMM1-P$184-Pad184)") (class "Default")
      (node (ref "SODIMM1") (pin "184") (pinfunction "P$184_184") (pintype "bidirectional"))
    )
    (net (code "187") (name "unconnected-(SODIMM1-P$185-Pad185)") (class "Default")
      (node (ref "SODIMM1") (pin "185") (pinfunction "P$185_185") (pintype "bidirectional"))
    )
    (net (code "188") (name "unconnected-(SODIMM1-P$186-Pad186)") (class "Default")
      (node (ref "SODIMM1") (pin "186") (pinfunction "P$186_186") (pintype "bidirectional"))
    )
    (net (code "189") (name "unconnected-(SODIMM1-P$187-Pad187)") (class "Default")
      (node (ref "SODIMM1") (pin "187") (pinfunction "P$187_187") (pintype "bidirectional"))
    )
    (net (code "190") (name "unconnected-(SODIMM1-P$188-Pad188)") (class "Default")
      (node (ref "SODIMM1") (pin "188") (pinfunction "P$188_188") (pintype "bidirectional"))
    )
    (net (code "191") (name "unconnected-(SODIMM1-P$189-Pad189)") (class "Default")
      (node (ref "SODIMM1") (pin "189") (pinfunction "P$189_189") (pintype "bidirectional"))
    )
    (net (code "192") (name "unconnected-(SODIMM1-P$190-Pad190)") (class "Default")
      (node (ref "SODIMM1") (pin "190") (pinfunction "P$190_190") (pintype "bidirectional"))
    )
    (net (code "193") (name "unconnected-(SODIMM1-P$191-Pad191)") (class "Default")
      (node (ref "SODIMM1") (pin "191") (pinfunction "P$191_191") (pintype "bidirectional"))
    )
    (net (code "194") (name "unconnected-(SODIMM1-P$192-Pad192)") (class "Default")
      (node (ref "SODIMM1") (pin "192") (pinfunction "P$192_192") (pintype "bidirectional"))
    )
    (net (code "195") (name "unconnected-(SODIMM1-P$193-Pad193)") (class "Default")
      (node (ref "SODIMM1") (pin "193") (pinfunction "P$193_193") (pintype "bidirectional"))
    )
    (net (code "196") (name "unconnected-(SODIMM1-P$194-Pad194)") (class "Default")
      (node (ref "SODIMM1") (pin "194") (pinfunction "P$194_194") (pintype "bidirectional"))
    )
    (net (code "197") (name "unconnected-(SODIMM1-P$195-Pad195)") (class "Default")
      (node (ref "SODIMM1") (pin "195") (pinfunction "P$195_195") (pintype "bidirectional"))
    )
    (net (code "198") (name "unconnected-(SODIMM1-P$196-Pad196)") (class "Default")
      (node (ref "SODIMM1") (pin "196") (pinfunction "P$196_196") (pintype "bidirectional"))
    )
    (net (code "199") (name "unconnected-(SODIMM1-P$197-Pad197)") (class "Default")
      (node (ref "SODIMM1") (pin "197") (pinfunction "P$197_197") (pintype "bidirectional"))
    )
    (net (code "200") (name "unconnected-(SODIMM1-P$198-Pad198)") (class "Default")
      (node (ref "SODIMM1") (pin "198") (pinfunction "P$198_198") (pintype "bidirectional"))
    )
    (net (code "201") (name "unconnected-(SODIMM1-P$199-Pad199)") (class "Default")
      (node (ref "SODIMM1") (pin "199") (pinfunction "P$199_199") (pintype "bidirectional"))
    )
    (net (code "202") (name "unconnected-(SODIMM1-P$200-Pad200)") (class "Default")
      (node (ref "SODIMM1") (pin "200") (pinfunction "P$200_200") (pintype "bidirectional"))
    )
    (net (code "203") (name "unconnected-(U$1-PadCE_N)") (class "Default")
      (node (ref "U$1") (pin "CE_N") (pinfunction "CE_N_CE_N") (pintype "input"))
    )
    (net (code "204") (name "unconnected-(U$1-PadIO_0)") (class "Default")
      (node (ref "U$1") (pin "IO_0") (pinfunction "IO_0_IO_0") (pintype "bidirectional"))
    )
    (net (code "205") (name "unconnected-(U$1-PadIO_1)") (class "Default")
      (node (ref "U$1") (pin "IO_1") (pinfunction "IO_1_IO_1") (pintype "bidirectional"))
    )
    (net (code "206") (name "unconnected-(U$1-PadIO_2)") (class "Default")
      (node (ref "U$1") (pin "IO_2") (pinfunction "IO_2_IO_2") (pintype "bidirectional"))
    )
    (net (code "207") (name "unconnected-(U$1-PadIO_3)") (class "Default")
      (node (ref "U$1") (pin "IO_3") (pinfunction "IO_3_IO_3") (pintype "bidirectional"))
    )
    (net (code "208") (name "unconnected-(U$1-PadIO_4)") (class "Default")
      (node (ref "U$1") (pin "IO_4") (pinfunction "IO_4_IO_4") (pintype "bidirectional"))
    )
    (net (code "209") (name "unconnected-(U$1-PadIO_5)") (class "Default")
      (node (ref "U$1") (pin "IO_5") (pinfunction "IO_5_IO_5") (pintype "bidirectional"))
    )
    (net (code "210") (name "unconnected-(U$1-PadIO_6)") (class "Default")
      (node (ref "U$1") (pin "IO_6") (pinfunction "IO_6_IO_6") (pintype "bidirectional"))
    )
    (net (code "211") (name "unconnected-(U$1-PadIO_7)") (class "Default")
      (node (ref "U$1") (pin "IO_7") (pinfunction "IO_7_IO_7") (pintype "bidirectional"))
    )
    (net (code "212") (name "unconnected-(U$1-PadOE_N)") (class "Default")
      (node (ref "U$1") (pin "OE_N") (pinfunction "OE_N_OE_N") (pintype "input"))
    )
    (net (code "213") (name "unconnected-(U$1-PadWE_N)") (class "Default")
      (node (ref "U$1") (pin "WE_N") (pinfunction "WE_N_WE_N") (pintype "input"))
    )
    (net (code "214") (name "unconnected-(U$2-PadCE_N)") (class "Default")
      (node (ref "U$2") (pin "CE_N") (pinfunction "CE_N_CE_N") (pintype "input"))
    )
    (net (code "215") (name "unconnected-(U$2-PadIO_0)") (class "Default")
      (node (ref "U$2") (pin "IO_0") (pinfunction "IO_0_IO_0") (pintype "bidirectional"))
    )
    (net (code "216") (name "unconnected-(U$2-PadIO_1)") (class "Default")
      (node (ref "U$2") (pin "IO_1") (pinfunction "IO_1_IO_1") (pintype "bidirectional"))
    )
    (net (code "217") (name "unconnected-(U$2-PadIO_2)") (class "Default")
      (node (ref "U$2") (pin "IO_2") (pinfunction "IO_2_IO_2") (pintype "bidirectional"))
    )
    (net (code "218") (name "unconnected-(U$2-PadIO_3)") (class "Default")
      (node (ref "U$2") (pin "IO_3") (pinfunction "IO_3_IO_3") (pintype "bidirectional"))
    )
    (net (code "219") (name "unconnected-(U$2-PadIO_4)") (class "Default")
      (node (ref "U$2") (pin "IO_4") (pinfunction "IO_4_IO_4") (pintype "bidirectional"))
    )
    (net (code "220") (name "unconnected-(U$2-PadIO_5)") (class "Default")
      (node (ref "U$2") (pin "IO_5") (pinfunction "IO_5_IO_5") (pintype "bidirectional"))
    )
    (net (code "221") (name "unconnected-(U$2-PadIO_6)") (class "Default")
      (node (ref "U$2") (pin "IO_6") (pinfunction "IO_6_IO_6") (pintype "bidirectional"))
    )
    (net (code "222") (name "unconnected-(U$2-PadIO_7)") (class "Default")
      (node (ref "U$2") (pin "IO_7") (pinfunction "IO_7_IO_7") (pintype "bidirectional"))
    )
    (net (code "223") (name "unconnected-(U$2-PadOE_N)") (class "Default")
      (node (ref "U$2") (pin "OE_N") (pinfunction "OE_N_OE_N") (pintype "input"))
    )
    (net (code "224") (name "unconnected-(U$2-PadWE_N)") (class "Default")
      (node (ref "U$2") (pin "WE_N") (pinfunction "WE_N_WE_N") (pintype "input"))
    )
    (net (code "225") (name "unconnected-(U$3-PadCE_N)") (class "Default")
      (node (ref "U$3") (pin "CE_N") (pinfunction "CE_N_CE_N") (pintype "input"))
    )
    (net (code "226") (name "unconnected-(U$3-PadIO_0)") (class "Default")
      (node (ref "U$3") (pin "IO_0") (pinfunction "IO_0_IO_0") (pintype "bidirectional"))
    )
    (net (code "227") (name "unconnected-(U$3-PadIO_1)") (class "Default")
      (node (ref "U$3") (pin "IO_1") (pinfunction "IO_1_IO_1") (pintype "bidirectional"))
    )
    (net (code "228") (name "unconnected-(U$3-PadIO_2)") (class "Default")
      (node (ref "U$3") (pin "IO_2") (pinfunction "IO_2_IO_2") (pintype "bidirectional"))
    )
    (net (code "229") (name "unconnected-(U$3-PadIO_3)") (class "Default")
      (node (ref "U$3") (pin "IO_3") (pinfunction "IO_3_IO_3") (pintype "bidirectional"))
    )
    (net (code "230") (name "unconnected-(U$3-PadIO_4)") (class "Default")
      (node (ref "U$3") (pin "IO_4") (pinfunction "IO_4_IO_4") (pintype "bidirectional"))
    )
    (net (code "231") (name "unconnected-(U$3-PadIO_5)") (class "Default")
      (node (ref "U$3") (pin "IO_5") (pinfunction "IO_5_IO_5") (pintype "bidirectional"))
    )
    (net (code "232") (name "unconnected-(U$3-PadIO_6)") (class "Default")
      (node (ref "U$3") (pin "IO_6") (pinfunction "IO_6_IO_6") (pintype "bidirectional"))
    )
    (net (code "233") (name "unconnected-(U$3-PadIO_7)") (class "Default")
      (node (ref "U$3") (pin "IO_7") (pinfunction "IO_7_IO_7") (pintype "bidirectional"))
    )
    (net (code "234") (name "unconnected-(U$3-PadOE_N)") (class "Default")
      (node (ref "U$3") (pin "OE_N") (pinfunction "OE_N_OE_N") (pintype "input"))
    )
    (net (code "235") (name "unconnected-(U$3-PadWE_N)") (class "Default")
      (node (ref "U$3") (pin "WE_N") (pinfunction "WE_N_WE_N") (pintype "input"))
    )
    (net (code "236") (name "unconnected-(U$4-PadCE_N)") (class "Default")
      (node (ref "U$4") (pin "CE_N") (pinfunction "CE_N_CE_N") (pintype "input"))
    )
    (net (code "237") (name "unconnected-(U$4-PadIO_0)") (class "Default")
      (node (ref "U$4") (pin "IO_0") (pinfunction "IO_0_IO_0") (pintype "bidirectional"))
    )
    (net (code "238") (name "unconnected-(U$4-PadIO_1)") (class "Default")
      (node (ref "U$4") (pin "IO_1") (pinfunction "IO_1_IO_1") (pintype "bidirectional"))
    )
    (net (code "239") (name "unconnected-(U$4-PadIO_2)") (class "Default")
      (node (ref "U$4") (pin "IO_2") (pinfunction "IO_2_IO_2") (pintype "bidirectional"))
    )
    (net (code "240") (name "unconnected-(U$4-PadIO_3)") (class "Default")
      (node (ref "U$4") (pin "IO_3") (pinfunction "IO_3_IO_3") (pintype "bidirectional"))
    )
    (net (code "241") (name "unconnected-(U$4-PadIO_4)") (class "Default")
      (node (ref "U$4") (pin "IO_4") (pinfunction "IO_4_IO_4") (pintype "bidirectional"))
    )
    (net (code "242") (name "unconnected-(U$4-PadIO_5)") (class "Default")
      (node (ref "U$4") (pin "IO_5") (pinfunction "IO_5_IO_5") (pintype "bidirectional"))
    )
    (net (code "243") (name "unconnected-(U$4-PadIO_6)") (class "Default")
      (node (ref "U$4") (pin "IO_6") (pinfunction "IO_6_IO_6") (pintype "bidirectional"))
    )
    (net (code "244") (name "unconnected-(U$4-PadIO_7)") (class "Default")
      (node (ref "U$4") (pin "IO_7") (pinfunction "IO_7_IO_7") (pintype "bidirectional"))
    )
    (net (code "245") (name "unconnected-(U$4-PadOE_N)") (class "Default")
      (node (ref "U$4") (pin "OE_N") (pinfunction "OE_N_OE_N") (pintype "input"))
    )
    (net (code "246") (name "unconnected-(U$4-PadWE_N)") (class "Default")
      (node (ref "U$4") (pin "WE_N") (pinfunction "WE_N_WE_N") (pintype "input"))
    )
  )
)
